# BSPD_Retencion_SCH.net
KiCad netlist of a schematic drawn in Altium Designer
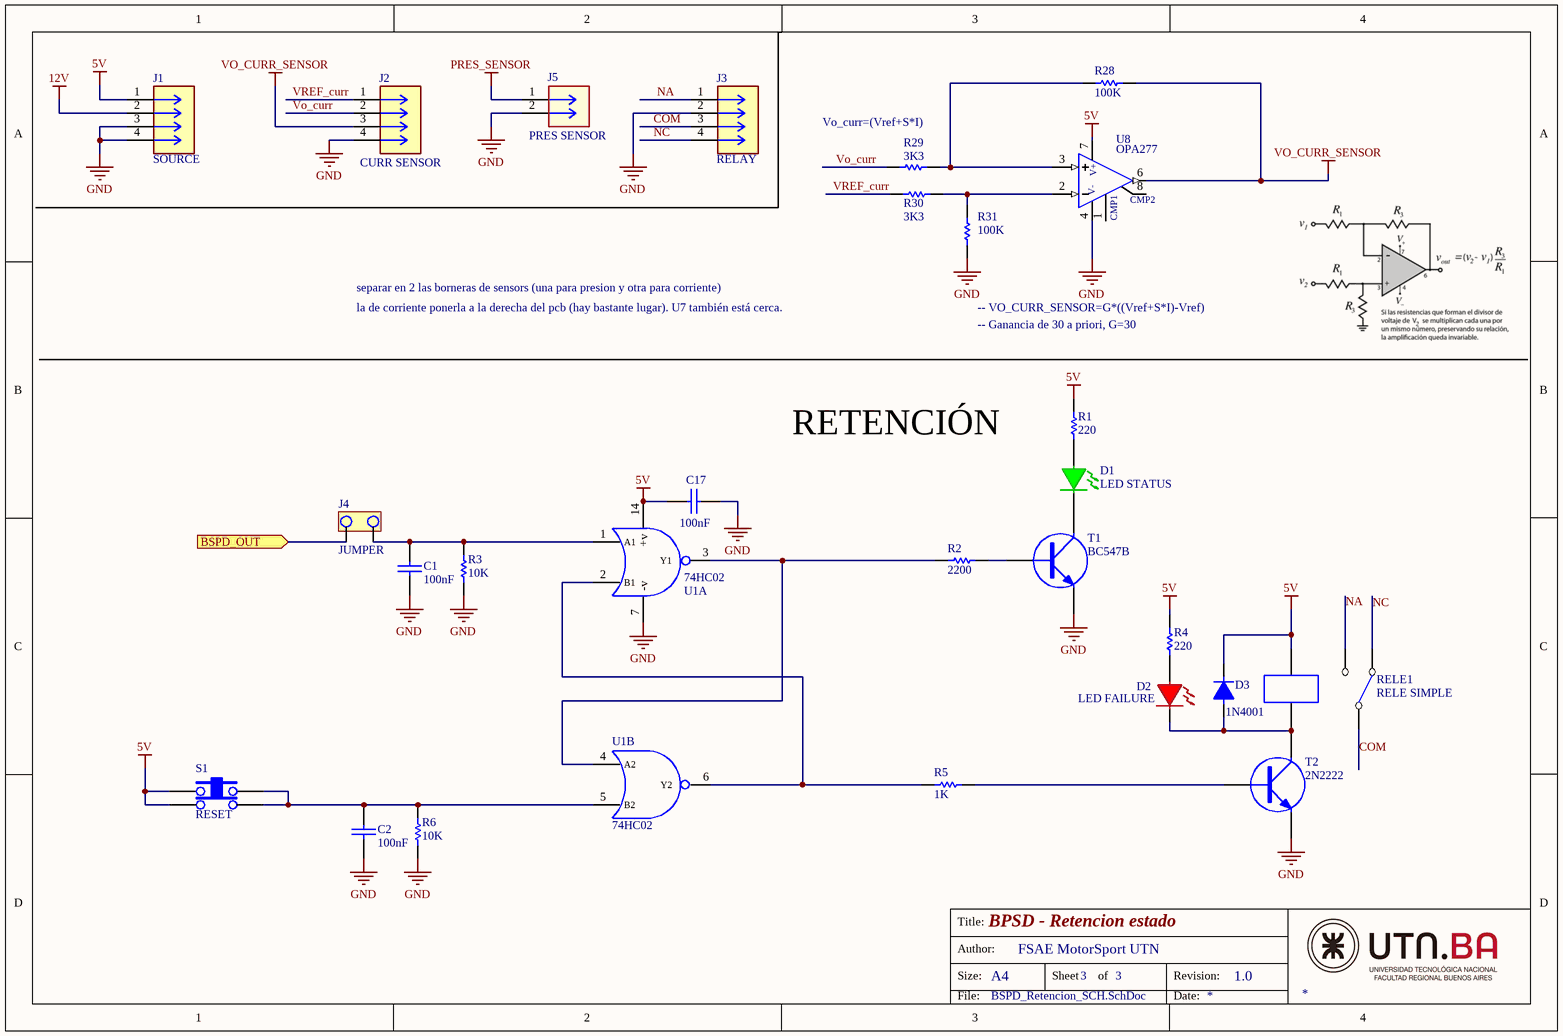
[diagram p0: BSPD_Retencion_SCH.SchDoc]

(export (version "E")
  (design (tool "Eeschema 10.0.6"))
  (components
    (comp (ref "C1") (value "100nF") (footprint "CAP200") (libsource (lib "BSPD_schlibrary") (part "CAP")))
    (comp (ref "C2") (value "100nF") (footprint "CAP200") (libsource (lib "BSPD_schlibrary") (part "CAP")))
    (comp (ref "C17") (value "100nF") (footprint "CAP200") (libsource (lib "BSPD_schlibrary") (part "CAP")))
    (comp (ref "D1")
      (value "LED STATUS")
      (footprint "LED 3 - Green")
      (description "LED VERDE")
      (libsource (lib "BSPD_schlibrary") (part "LED VERDE"))
    )
    (comp (ref "D2")
      (value "LED FAILURE")
      (footprint "LED 3 - Red")
      (description "LED ROJO")
      (libsource (lib "BSPD_schlibrary") (part "LED ROJO"))
    )
    (comp (ref "D3")
      (value "1N4001")
      (footprint "DO41")
      (description "Diodo")
      (libsource (lib "BSPD_schlibrary") (part "1N4001"))
    )
    (comp (ref "J1")
      (value "SOURCE")
      (footprint "CONN_SD-44067-001_04_MOL")
      (description "Molex mini 50 de 4 pines (440670401)")
      (fields (field (name "MP") "347920040"))
      (libsource (lib "BSPD_schlibrary") (part "MolexMini 4"))
    )
    (comp (ref "J2")
      (value "CURR SENSOR")
      (footprint "CONN_SD-44067-001_04_MOL")
      (description "Molex mini 50 de 4 pines (440670401)")
      (fields (field (name "MP") "347920040"))
      (libsource (lib "BSPD_schlibrary") (part "MolexMini 4"))
    )
    (comp (ref "J3")
      (value "RELAY")
      (footprint "CONN_SD-44067-001_04_MOL")
      (description "Molex mini 50 de 4 pines (440670401)")
      (fields (field (name "MP") "347920040"))
      (libsource (lib "BSPD_schlibrary") (part "MolexMini 4"))
    )
    (comp (ref "J4")
      (value "JUMPER")
      (footprint "JUMPER2")
      (libsource (lib "BSPD_schlibrary") (part "JUMPER"))
    )
    (comp (ref "J5")
      (value "PRES SENSOR")
      (footprint "CONN_SD-44067-001_02_MOL")
      (fields
        (field (name "MANUFACTURER_PART_NUMBER") "440670201")
        (field (name "COPYRIGHT") "Copyright (C) 2025 Ultra Librarian. All rights reserved.")
      )
      (libsource (lib "BSPD_schlibrary") (part "MolexMini 2"))
    )
    (comp (ref "R1") (value "220") (footprint "RES400") (libsource (lib "BSPD_schlibrary") (part "RES")))
    (comp (ref "R2") (value "2200") (footprint "RES400") (libsource (lib "BSPD_schlibrary") (part "RES")))
    (comp (ref "R3") (value "10K") (footprint "RES400") (libsource (lib "BSPD_schlibrary") (part "RES")))
    (comp (ref "R4") (value "220") (footprint "RES400") (libsource (lib "BSPD_schlibrary") (part "RES")))
    (comp (ref "R5") (value "1K") (footprint "RES400") (libsource (lib "BSPD_schlibrary") (part "RES")))
    (comp (ref "R6") (value "10K") (footprint "RES400") (libsource (lib "BSPD_schlibrary") (part "RES")))
    (comp (ref "R28") (value "100K") (footprint "RES400") (libsource (lib "BSPD_schlibrary") (part "RES")))
    (comp (ref "R29") (value "3K3") (footprint "RES400") (libsource (lib "BSPD_schlibrary") (part "RES")))
    (comp (ref "R30") (value "3K3") (footprint "RES400") (libsource (lib "BSPD_schlibrary") (part "RES")))
    (comp (ref "R31") (value "100K") (footprint "RES400") (libsource (lib "BSPD_schlibrary") (part "RES")))
    (comp (ref "RELE1")
      (value "RELE SIMPLE")
      (footprint "RELE SERIE 943")
      (libsource (lib "BSPD_schlibrary") (part "RELE SIMPLE"))
    )
    (comp (ref "S1")
      (value "RESET")
      (footprint "TACTSWITCH")
      (libsource (lib "BSPD_schlibrary") (part "TACT SWITCH"))
    )
    (comp (ref "T1")
      (value "BC547B")
      (footprint "TO92")
      (libsource (lib "BSPD_schlibrary") (part "TRANSISTOR NPN"))
    )
    (comp (ref "T2")
      (value "2N2222")
      (footprint "TO-18")
      (libsource (lib "BSPD_schlibrary") (part "TRANSISTOR NPN"))
    )
    (comp (ref "U1")
      (value "74HC02")
      (footprint "DIP14")
      (description "Compuerta NOR")
      (fields (field (name "AUTOR") "SALERNO, Santiago"))
      (libsource (lib "BSPD_schlibrary") (part "74HC02"))
    )
    (comp (ref "U8")
      (value "OPA277")
      (footprint "DIP8")
      (description "Op Amp Single Low Offset Voltage Amplifier Â±18V 8-Pin PDIP Tube")
      (fields (field (name "MF") "Texas Instruments"))
      (libsource (lib "BSPD_schlibrary") (part "OPA277"))
    )
  )
  (nets
    (net (code "1") (name "/BSPD_OUT") (class "Default")
      (node (ref "J4") (pin "2") (pinfunction "2_2") (pintype "passive"))
    )
    (net (code "2") (name "/COM") (class "Default")
      (node (ref "J3") (pin "3") (pinfunction "3_3") (pintype "passive"))
      (node (ref "RELE1") (pin "C1") (pinfunction "C1_C1") (pintype "passive"))
    )
    (net (code "3") (name "/NA") (class "Default")
      (node (ref "J3") (pin "1") (pinfunction "1_1") (pintype "passive"))
      (node (ref "RELE1") (pin "NA1") (pinfunction "NA1_NA1") (pintype "passive"))
    )
    (net (code "4") (name "/NC") (class "Default")
      (node (ref "J3") (pin "4") (pinfunction "4_4") (pintype "passive"))
      (node (ref "RELE1") (pin "NC1") (pinfunction "NC1_NC1") (pintype "passive"))
    )
    (net (code "5") (name "/VREF_curr") (class "Default")
      (node (ref "J2") (pin "1") (pinfunction "1_1") (pintype "passive"))
      (node (ref "R30") (pin "2") (pinfunction "2_2") (pintype "passive"))
    )
    (net (code "6") (name "/Vo_curr") (class "Default")
      (node (ref "J2") (pin "2") (pinfunction "2_2") (pintype "passive"))
      (node (ref "R29") (pin "2") (pinfunction "2_2") (pintype "passive"))
    )
    (net (code "7") (name "5V") (class "Default")
      (node (ref "C17") (pin "1") (pinfunction "1_1") (pintype "passive"))
      (node (ref "D3") (pin "2") (pinfunction "2_2") (pintype "passive"))
      (node (ref "J1") (pin "1") (pinfunction "1_1") (pintype "passive"))
      (node (ref "R1") (pin "2") (pinfunction "2_2") (pintype "passive"))
      (node (ref "R4") (pin "2") (pinfunction "2_2") (pintype "passive"))
      (node (ref "RELE1") (pin "B1") (pinfunction "B1_B1") (pintype "passive"))
      (node (ref "S1") (pin "1") (pinfunction "1_1") (pintype "passive"))
      (node (ref "S1") (pin "2") (pinfunction "2_2") (pintype "passive"))
      (node (ref "U1") (pin "14") (pinfunction "+v_14") (pintype "passive"))
      (node (ref "U8") (pin "7") (pinfunction "V+_7") (pintype "power_in"))
    )
    (net (code "8") (name "12V") (class "Default")
      (node (ref "J1") (pin "2") (pinfunction "2_2") (pintype "passive"))
    )
    (net (code "9") (name "GND") (class "Default")
      (node (ref "C1") (pin "2") (pinfunction "2_2") (pintype "passive"))
      (node (ref "C17") (pin "2") (pinfunction "2_2") (pintype "passive"))
      (node (ref "C2") (pin "2") (pinfunction "2_2") (pintype "passive"))
      (node (ref "J1") (pin "3") (pinfunction "3_3") (pintype "passive"))
      (node (ref "J1") (pin "4") (pinfunction "4_4") (pintype "passive"))
      (node (ref "J2") (pin "4") (pinfunction "4_4") (pintype "passive"))
      (node (ref "J3") (pin "2") (pinfunction "2_2") (pintype "passive"))
      (node (ref "J5") (pin "2") (pinfunction "2_2") (pintype "passive"))
      (node (ref "R3") (pin "1") (pinfunction "1_1") (pintype "passive"))
      (node (ref "R31") (pin "2") (pinfunction "2_2") (pintype "passive"))
      (node (ref "R6") (pin "1") (pinfunction "1_1") (pintype "passive"))
      (node (ref "T1") (pin "3") (pinfunction "E_3") (pintype "passive"))
      (node (ref "T2") (pin "3") (pinfunction "E_3") (pintype "passive"))
      (node (ref "U1") (pin "7") (pinfunction "-v_7") (pintype "passive"))
      (node (ref "U8") (pin "4") (pinfunction "V-_4") (pintype "power_in"))
    )
    (net (code "10") (name "Net-(D1-Pad1)") (class "Default")
      (node (ref "D1") (pin "1") (pinfunction "1_1") (pintype "passive"))
      (node (ref "R1") (pin "1") (pinfunction "1_1") (pintype "passive"))
    )
    (net (code "11") (name "Net-(D2-Pad1)") (class "Default")
      (node (ref "D2") (pin "1") (pinfunction "1_1") (pintype "passive"))
      (node (ref "R4") (pin "1") (pinfunction "1_1") (pintype "passive"))
    )
    (net (code "12") (name "Net-(T1-B)") (class "Default")
      (node (ref "R2") (pin "2") (pinfunction "2_2") (pintype "passive"))
      (node (ref "T1") (pin "1") (pinfunction "B_1") (pintype "passive"))
    )
    (net (code "13") (name "Net-(T1-C)") (class "Default")
      (node (ref "D1") (pin "2") (pinfunction "2_2") (pintype "passive"))
      (node (ref "T1") (pin "2") (pinfunction "C_2") (pintype "passive"))
    )
    (net (code "14") (name "Net-(T2-B)") (class "Default")
      (node (ref "R5") (pin "2") (pinfunction "2_2") (pintype "passive"))
      (node (ref "T2") (pin "1") (pinfunction "B_1") (pintype "passive"))
    )
    (net (code "15") (name "Net-(T2-C)") (class "Default")
      (node (ref "D2") (pin "2") (pinfunction "2_2") (pintype "passive"))
      (node (ref "D3") (pin "1") (pinfunction "1_1") (pintype "passive"))
      (node (ref "RELE1") (pin "B2") (pinfunction "B2_B2") (pintype "passive"))
      (node (ref "T2") (pin "2") (pinfunction "C_2") (pintype "passive"))
    )
    (net (code "16") (name "Net-(U1A-A1)") (class "Default")
      (node (ref "C1") (pin "1") (pinfunction "1_1") (pintype "passive"))
      (node (ref "J4") (pin "1") (pinfunction "1_1") (pintype "passive"))
      (node (ref "R3") (pin "2") (pinfunction "2_2") (pintype "passive"))
      (node (ref "U1") (pin "1") (pinfunction "A1_1") (pintype "passive"))
    )
    (net (code "17") (name "Net-(U1A-B1)") (class "Default")
      (node (ref "R5") (pin "1") (pinfunction "1_1") (pintype "passive"))
      (node (ref "U1") (pin "2") (pinfunction "B1_2") (pintype "passive"))
      (node (ref "U1") (pin "6") (pinfunction "Y2_6") (pintype "passive"))
    )
    (net (code "18") (name "Net-(U1A-Y1)") (class "Default")
      (node (ref "R2") (pin "1") (pinfunction "1_1") (pintype "passive"))
      (node (ref "U1") (pin "3") (pinfunction "Y1_3") (pintype "passive"))
      (node (ref "U1") (pin "4") (pinfunction "A2_4") (pintype "passive"))
    )
    (net (code "19") (name "Net-(U1B-B2)") (class "Default")
      (node (ref "C2") (pin "1") (pinfunction "1_1") (pintype "passive"))
      (node (ref "R6") (pin "2") (pinfunction "2_2") (pintype "passive"))
      (node (ref "S1") (pin "3") (pinfunction "3_3") (pintype "passive"))
      (node (ref "S1") (pin "4") (pinfunction "4_4") (pintype "passive"))
      (node (ref "U1") (pin "5") (pinfunction "B2_5") (pintype "passive"))
    )
    (net (code "20") (name "Net-(U8-+IN)") (class "Default")
      (node (ref "R28") (pin "2") (pinfunction "2_2") (pintype "passive"))
      (node (ref "R29") (pin "1") (pinfunction "1_1") (pintype "passive"))
      (node (ref "U8") (pin "3") (pinfunction "+IN_3") (pintype "input"))
    )
    (net (code "21") (name "Net-(U8--IN)") (class "Default")
      (node (ref "R30") (pin "1") (pinfunction "1_1") (pintype "passive"))
      (node (ref "R31") (pin "1") (pinfunction "1_1") (pintype "passive"))
      (node (ref "U8") (pin "2") (pinfunction "-IN_2") (pintype "input"))
    )
    (net (code "22") (name "PRES_SENSOR") (class "Default")
      (node (ref "J5") (pin "1") (pinfunction "1_1") (pintype "passive"))
    )
    (net (code "23") (name "VO_CURR_SENSOR") (class "Default")
      (node (ref "J2") (pin "3") (pinfunction "3_3") (pintype "passive"))
      (node (ref "R28") (pin "1") (pinfunction "1_1") (pintype "passive"))
      (node (ref "U8") (pin "6") (pinfunction "OUT_6") (pintype "output"))
    )
    (net (code "24") (name "unconnected-(U8-CMP1-Pad1)") (class "Default")
      (node (ref "U8") (pin "1") (pinfunction "CMP1_1") (pintype "passive"))
    )
    (net (code "25") (name "unconnected-(U8-CMP2-Pad8)") (class "Default")
      (node (ref "U8") (pin "8") (pinfunction "CMP2_8") (pintype "passive"))
    )
  )
)
